# CH634W6G.net
KiCad netlist of a schematic drawn in Altium Designer
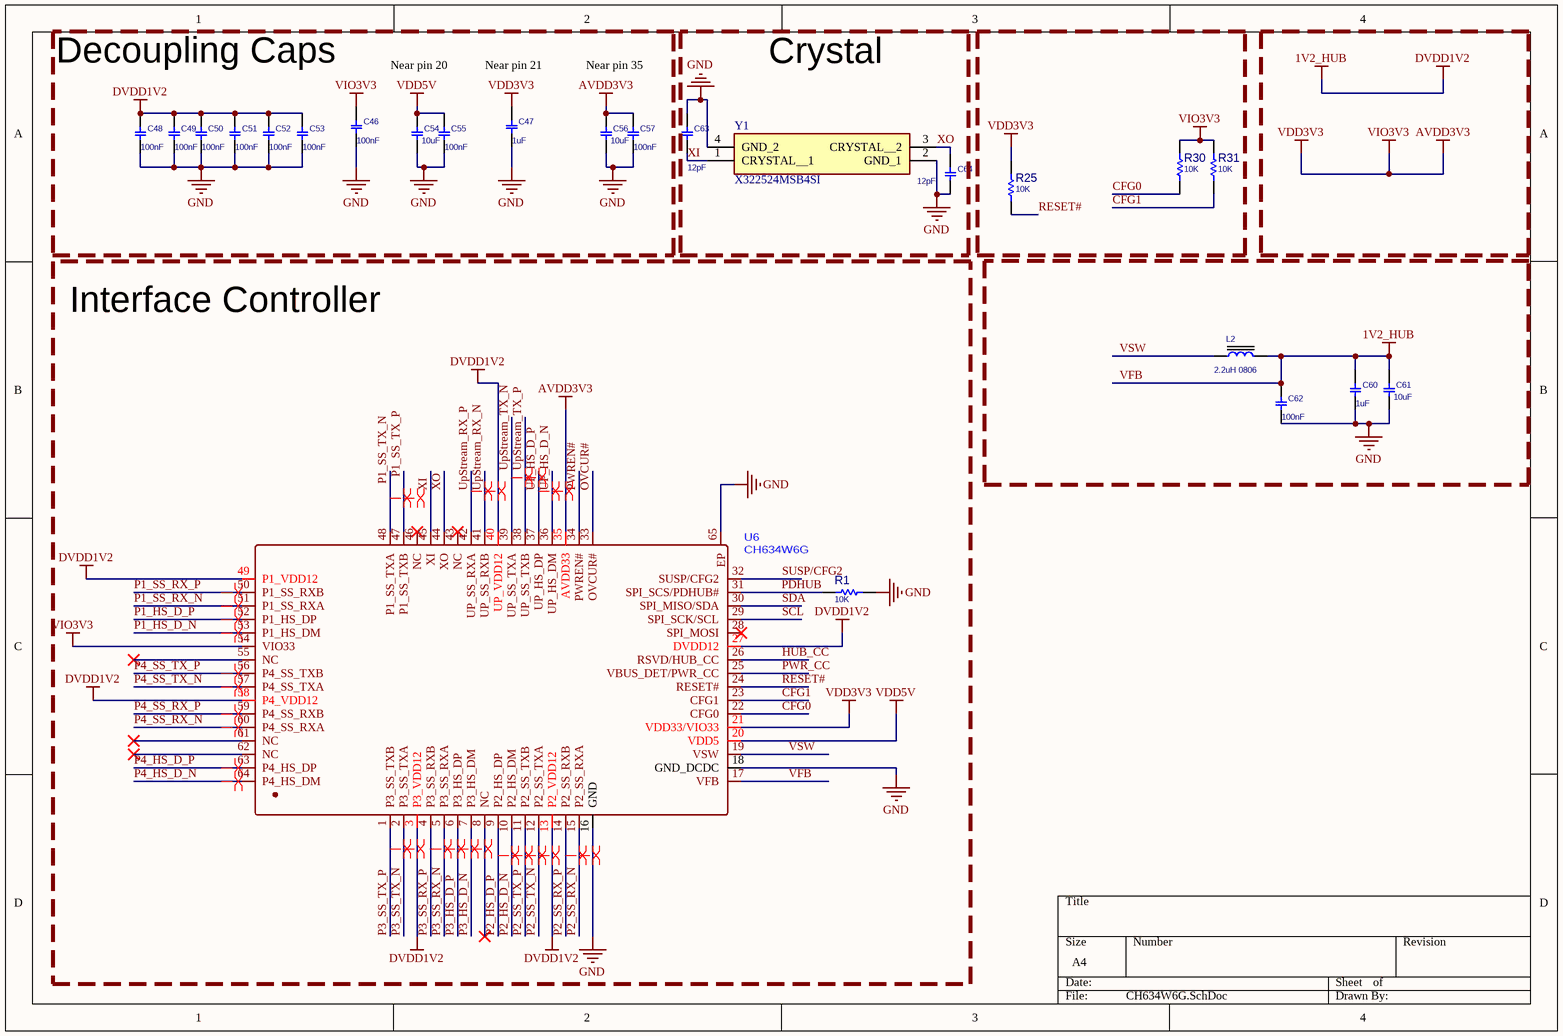
[diagram p0: CH634W6G.SchDoc]

(export (version "E")
  (design (tool "Eeschema 10.0.6"))
  (components
    (comp (ref "C46")
      (value "100nF")
      (footprint "C0402")
      (libsource (lib "passive_smd") (part "CAP_SMD_MLCC_0402"))
    )
    (comp (ref "C47")
      (value "1uF")
      (footprint "C0402")
      (libsource (lib "passive_smd") (part "CAP_SMD_MLCC_0402"))
    )
    (comp (ref "C48")
      (value "100nF")
      (footprint "C0402")
      (libsource (lib "passive_smd") (part "CAP_SMD_MLCC_0402"))
    )
    (comp (ref "C49")
      (value "100nF")
      (footprint "C0402")
      (libsource (lib "passive_smd") (part "CAP_SMD_MLCC_0402"))
    )
    (comp (ref "C50")
      (value "100nF")
      (footprint "C0402")
      (libsource (lib "passive_smd") (part "CAP_SMD_MLCC_0402"))
    )
    (comp (ref "C51")
      (value "100nF")
      (footprint "C0402")
      (libsource (lib "passive_smd") (part "CAP_SMD_MLCC_0402"))
    )
    (comp (ref "C52")
      (value "100nF")
      (footprint "C0402")
      (libsource (lib "passive_smd") (part "CAP_SMD_MLCC_0402"))
    )
    (comp (ref "C53")
      (value "100nF")
      (footprint "C0402")
      (libsource (lib "passive_smd") (part "CAP_SMD_MLCC_0402"))
    )
    (comp (ref "C54")
      (value "10uF")
      (footprint "C0603")
      (libsource (lib "passive_smd") (part "CAP_SMD_MLCC_0603"))
    )
    (comp (ref "C55")
      (value "100nF")
      (footprint "C0402")
      (libsource (lib "passive_smd") (part "CAP_SMD_MLCC_0402"))
    )
    (comp (ref "C56")
      (value "10uF")
      (footprint "C0603")
      (libsource (lib "passive_smd") (part "CAP_SMD_MLCC_0603"))
    )
    (comp (ref "C57")
      (value "100nF")
      (footprint "C0402")
      (libsource (lib "passive_smd") (part "CAP_SMD_MLCC_0402"))
    )
    (comp (ref "C60")
      (value "1uF")
      (footprint "C0402")
      (libsource (lib "passive_smd") (part "CAP_SMD_MLCC_0402"))
    )
    (comp (ref "C61")
      (value "10uF")
      (footprint "C0603")
      (libsource (lib "passive_smd") (part "CAP_SMD_MLCC_0603"))
    )
    (comp (ref "C62")
      (value "100nF")
      (footprint "C0402")
      (libsource (lib "passive_smd") (part "CAP_SMD_MLCC_0402"))
    )
    (comp (ref "C63")
      (value "12pF")
      (footprint "C0402")
      (libsource (lib "passive_smd") (part "CAP_SMD_MLCC_0402"))
    )
    (comp (ref "C64")
      (value "12pF")
      (footprint "C0402")
      (libsource (lib "passive_smd") (part "CAP_SMD_MLCC_0402"))
    )
    (comp (ref "L2")
      (value "2.2uH 0806")
      (footprint "L0806")
      (description "SLW201610S2R2MST")
      (libsource (lib "inductor_power") (part "IND_SMD_1uH_2.3A_0806"))
    )
    (comp (ref "R1")
      (value "10K")
      (footprint "R0402")
      (description "RESISTOR, SMD")
      (libsource (lib "passive_smd") (part "RES_SMD_0402"))
    )
    (comp (ref "R25")
      (value "10K")
      (footprint "R0402")
      (description "RESISTOR, SMD")
      (libsource (lib "passive_smd") (part "RES_SMD_0402"))
    )
    (comp (ref "R30")
      (value "10K")
      (footprint "R0402")
      (description "RESISTOR, SMD")
      (libsource (lib "passive_smd") (part "RES_SMD_0402"))
    )
    (comp (ref "R31")
      (value "10K")
      (footprint "R0402")
      (description "RESISTOR, SMD")
      (libsource (lib "passive_smd") (part "RES_SMD_0402"))
    )
    (comp (ref "U6") (value "CH634W6G") (footprint "CH634w") (libsource (lib "Schlib1") (part "CH634W6G")))
    (comp (ref "Y1")
      (value "X322524MSB4SI")
      (footprint "SamacSys:X1E0000210264")
      (description "Crystal or Oscillator")
      (libsource (lib "*") (part "X1E0000210264"))
    )
  )
  (nets
    (net (code "1") (name "/CFG0") (class "Default")
      (node (ref "R30") (pin "2") (pinfunction "2_2") (pintype "passive"))
      (node (ref "U6") (pin "22") (pinfunction "CFG0_22") (pintype "passive"))
    )
    (net (code "2") (name "/CFG1") (class "Default")
      (node (ref "R31") (pin "2") (pinfunction "2_2") (pintype "passive"))
      (node (ref "U6") (pin "23") (pinfunction "CFG1_23") (pintype "passive"))
    )
    (net (code "3") (name "/HUB_CC") (class "Default")
      (node (ref "U6") (pin "26") (pinfunction "RSVD/HUB_CC_26") (pintype "passive"))
    )
    (net (code "4") (name "/OVCUR#") (class "Default")
      (node (ref "U6") (pin "33") (pinfunction "OVCUR#_33") (pintype "passive"))
    )
    (net (code "5") (name "/P1_HS_D_N") (class "Default")
      (node (ref "U6") (pin "53") (pinfunction "P1_HS_DM_53") (pintype "passive"))
    )
    (net (code "6") (name "/P1_HS_D_P") (class "Default")
      (node (ref "U6") (pin "52") (pinfunction "P1_HS_DP_52") (pintype "passive"))
    )
    (net (code "7") (name "/P1_SS_RX_N") (class "Default")
      (node (ref "U6") (pin "51") (pinfunction "P1_SS_RXA_51") (pintype "passive"))
    )
    (net (code "8") (name "/P1_SS_RX_P") (class "Default")
      (node (ref "U6") (pin "50") (pinfunction "P1_SS_RXB_50") (pintype "passive"))
    )
    (net (code "9") (name "/P1_SS_TX_N") (class "Default")
      (node (ref "U6") (pin "48") (pinfunction "P1_SS_TXA_48") (pintype "passive"))
    )
    (net (code "10") (name "/P1_SS_TX_P") (class "Default")
      (node (ref "U6") (pin "47") (pinfunction "P1_SS_TXB_47") (pintype "passive"))
    )
    (net (code "11") (name "/P2_HS_D_N") (class "Default")
      (node (ref "U6") (pin "10") (pinfunction "P2_HS_DM_10") (pintype "passive"))
    )
    (net (code "12") (name "/P2_HS_D_P") (class "Default")
      (node (ref "U6") (pin "9") (pinfunction "P2_HS_DP_9") (pintype "passive"))
    )
    (net (code "13") (name "/P2_SS_RX_N") (class "Default")
      (node (ref "U6") (pin "15") (pinfunction "P2_SS_RXA_15") (pintype "passive"))
    )
    (net (code "14") (name "/P2_SS_RX_P") (class "Default")
      (node (ref "U6") (pin "14") (pinfunction "P2_SS_RXB_14") (pintype "passive"))
    )
    (net (code "15") (name "/P2_SS_TX_N") (class "Default")
      (node (ref "U6") (pin "12") (pinfunction "P2_SS_TXA_12") (pintype "passive"))
    )
    (net (code "16") (name "/P2_SS_TX_P") (class "Default")
      (node (ref "U6") (pin "11") (pinfunction "P2_SS_TXB_11") (pintype "passive"))
    )
    (net (code "17") (name "/P3_HS_D_N") (class "Default")
      (node (ref "U6") (pin "7") (pinfunction "P3_HS_DM_7") (pintype "passive"))
    )
    (net (code "18") (name "/P3_HS_D_P") (class "Default")
      (node (ref "U6") (pin "6") (pinfunction "P3_HS_DP_6") (pintype "passive"))
    )
    (net (code "19") (name "/P3_SS_RX_N") (class "Default")
      (node (ref "U6") (pin "5") (pinfunction "P3_SS_RXA_5") (pintype "passive"))
    )
    (net (code "20") (name "/P3_SS_RX_P") (class "Default")
      (node (ref "U6") (pin "4") (pinfunction "P3_SS_RXB_4") (pintype "passive"))
    )
    (net (code "21") (name "/P3_SS_TX_N") (class "Default")
      (node (ref "U6") (pin "2") (pinfunction "P3_SS_TXA_2") (pintype "passive"))
    )
    (net (code "22") (name "/P3_SS_TX_P") (class "Default")
      (node (ref "U6") (pin "1") (pinfunction "P3_SS_TXB_1") (pintype "passive"))
    )
    (net (code "23") (name "/P4_HS_D_N") (class "Default")
      (node (ref "U6") (pin "64") (pinfunction "P4_HS_DM_64") (pintype "passive"))
    )
    (net (code "24") (name "/P4_HS_D_P") (class "Default")
      (node (ref "U6") (pin "63") (pinfunction "P4_HS_DP_63") (pintype "passive"))
    )
    (net (code "25") (name "/P4_SS_RX_N") (class "Default")
      (node (ref "U6") (pin "60") (pinfunction "P4_SS_RXA_60") (pintype "passive"))
    )
    (net (code "26") (name "/P4_SS_RX_P") (class "Default")
      (node (ref "U6") (pin "59") (pinfunction "P4_SS_RXB_59") (pintype "passive"))
    )
    (net (code "27") (name "/P4_SS_TX_N") (class "Default")
      (node (ref "U6") (pin "57") (pinfunction "P4_SS_TXA_57") (pintype "passive"))
    )
    (net (code "28") (name "/P4_SS_TX_P") (class "Default")
      (node (ref "U6") (pin "56") (pinfunction "P4_SS_TXB_56") (pintype "passive"))
    )
    (net (code "29") (name "/PDHUB") (class "Default")
      (node (ref "R1") (pin "1") (pinfunction "1_1") (pintype "passive"))
      (node (ref "U6") (pin "31") (pinfunction "SPI_SCS/PDHUB#_31") (pintype "passive"))
    )
    (net (code "30") (name "/PWREN#") (class "Default")
      (node (ref "U6") (pin "34") (pinfunction "PWREN#_34") (pintype "passive"))
    )
    (net (code "31") (name "/PWR_CC") (class "Default")
      (node (ref "U6") (pin "25") (pinfunction "VBUS_DET/PWR_CC_25") (pintype "passive"))
    )
    (net (code "32") (name "/RESET#") (class "Default")
      (node (ref "R25") (pin "2") (pinfunction "2_2") (pintype "passive"))
      (node (ref "U6") (pin "24") (pinfunction "RESET#_24") (pintype "passive"))
    )
    (net (code "33") (name "/SCL") (class "Default")
      (node (ref "U6") (pin "29") (pinfunction "SPI_SCK/SCL_29") (pintype "passive"))
    )
    (net (code "34") (name "/SDA") (class "Default")
      (node (ref "U6") (pin "30") (pinfunction "SPI_MISO/SDA_30") (pintype "passive"))
    )
    (net (code "35") (name "/SUSP{slash}CFG2") (class "Default")
      (node (ref "U6") (pin "32") (pinfunction "SUSP/CFG2_32") (pintype "passive"))
    )
    (net (code "36") (name "/UP_HS_D_N") (class "Default")
      (node (ref "U6") (pin "36") (pinfunction "UP_HS_DM_36") (pintype "passive"))
    )
    (net (code "37") (name "/UP_HS_D_P") (class "Default")
      (node (ref "U6") (pin "37") (pinfunction "UP_HS_DP_37") (pintype "passive"))
    )
    (net (code "38") (name "/UpStream_RX_N") (class "Default")
      (node (ref "U6") (pin "41") (pinfunction "UP_SS_RXB_41") (pintype "passive"))
    )
    (net (code "39") (name "/UpStream_RX_P") (class "Default")
      (node (ref "U6") (pin "42") (pinfunction "UP_SS_RXA_42") (pintype "passive"))
    )
    (net (code "40") (name "/UpStream_TX_N") (class "Default")
      (node (ref "U6") (pin "39") (pinfunction "UP_SS_TXA_39") (pintype "passive"))
    )
    (net (code "41") (name "/UpStream_TX_P") (class "Default")
      (node (ref "U6") (pin "38") (pinfunction "UP_SS_TXB_38") (pintype "passive"))
    )
    (net (code "42") (name "/VSW") (class "Default")
      (node (ref "L2") (pin "1") (pinfunction "1_1") (pintype "passive"))
      (node (ref "U6") (pin "19") (pinfunction "VSW_19") (pintype "passive"))
    )
    (net (code "43") (name "/XI") (class "Default")
      (node (ref "C63") (pin "1") (pinfunction "1_1") (pintype "passive"))
      (node (ref "U6") (pin "45") (pinfunction "XI_45") (pintype "passive"))
      (node (ref "Y1") (pin "1") (pinfunction "CRYSTAL__1_1") (pintype "passive"))
    )
    (net (code "44") (name "/XO") (class "Default")
      (node (ref "C64") (pin "1") (pinfunction "1_1") (pintype "passive"))
      (node (ref "U6") (pin "44") (pinfunction "XO_44") (pintype "passive"))
      (node (ref "Y1") (pin "3") (pinfunction "CRYSTAL__2_3") (pintype "passive"))
    )
    (net (code "45") (name "1V2_HUB") (class "Default")
      (node (ref "C48") (pin "2") (pinfunction "2_2") (pintype "passive"))
      (node (ref "C49") (pin "2") (pinfunction "2_2") (pintype "passive"))
      (node (ref "C50") (pin "2") (pinfunction "2_2") (pintype "passive"))
      (node (ref "C51") (pin "2") (pinfunction "2_2") (pintype "passive"))
      (node (ref "C52") (pin "2") (pinfunction "2_2") (pintype "passive"))
      (node (ref "C53") (pin "2") (pinfunction "2_2") (pintype "passive"))
      (node (ref "C60") (pin "2") (pinfunction "2_2") (pintype "passive"))
      (node (ref "C61") (pin "2") (pinfunction "2_2") (pintype "passive"))
      (node (ref "C62") (pin "2") (pinfunction "2_2") (pintype "passive"))
      (node (ref "L2") (pin "2") (pinfunction "2_2") (pintype "passive"))
      (node (ref "U6") (pin "13") (pinfunction "P2_VDD12_13") (pintype "passive"))
      (node (ref "U6") (pin "17") (pinfunction "VFB_17") (pintype "passive"))
      (node (ref "U6") (pin "27") (pinfunction "DVDD12_27") (pintype "passive"))
      (node (ref "U6") (pin "3") (pinfunction "P3_VDD12_3") (pintype "passive"))
      (node (ref "U6") (pin "40") (pinfunction "UP_VDD12_40") (pintype "passive"))
      (node (ref "U6") (pin "49") (pinfunction "P1_VDD12_49") (pintype "passive"))
      (node (ref "U6") (pin "58") (pinfunction "P4_VDD12_58") (pintype "passive"))
    )
    (net (code "46") (name "AVDD3V3") (class "Default")
      (node (ref "C46") (pin "2") (pinfunction "2_2") (pintype "passive"))
      (node (ref "C47") (pin "2") (pinfunction "2_2") (pintype "passive"))
      (node (ref "C56") (pin "2") (pinfunction "2_2") (pintype "passive"))
      (node (ref "C57") (pin "2") (pinfunction "2_2") (pintype "passive"))
      (node (ref "R25") (pin "1") (pinfunction "1_1") (pintype "passive"))
      (node (ref "R30") (pin "1") (pinfunction "1_1") (pintype "passive"))
      (node (ref "R31") (pin "1") (pinfunction "1_1") (pintype "passive"))
      (node (ref "U6") (pin "21") (pinfunction "VDD33/VIO33_21") (pintype "passive"))
      (node (ref "U6") (pin "35") (pinfunction "AVDD33_35") (pintype "passive"))
      (node (ref "U6") (pin "54") (pinfunction "VIO33_54") (pintype "passive"))
    )
    (net (code "47") (name "GND") (class "Default")
      (node (ref "C46") (pin "1") (pinfunction "1_1") (pintype "passive"))
      (node (ref "C47") (pin "1") (pinfunction "1_1") (pintype "passive"))
      (node (ref "C48") (pin "1") (pinfunction "1_1") (pintype "passive"))
      (node (ref "C49") (pin "1") (pinfunction "1_1") (pintype "passive"))
      (node (ref "C50") (pin "1") (pinfunction "1_1") (pintype "passive"))
      (node (ref "C51") (pin "1") (pinfunction "1_1") (pintype "passive"))
      (node (ref "C52") (pin "1") (pinfunction "1_1") (pintype "passive"))
      (node (ref "C53") (pin "1") (pinfunction "1_1") (pintype "passive"))
      (node (ref "C54") (pin "1") (pinfunction "1_1") (pintype "passive"))
      (node (ref "C55") (pin "1") (pinfunction "1_1") (pintype "passive"))
      (node (ref "C56") (pin "1") (pinfunction "1_1") (pintype "passive"))
      (node (ref "C57") (pin "1") (pinfunction "1_1") (pintype "passive"))
      (node (ref "C60") (pin "1") (pinfunction "1_1") (pintype "passive"))
      (node (ref "C61") (pin "1") (pinfunction "1_1") (pintype "passive"))
      (node (ref "C62") (pin "1") (pinfunction "1_1") (pintype "passive"))
      (node (ref "C63") (pin "2") (pinfunction "2_2") (pintype "passive"))
      (node (ref "C64") (pin "2") (pinfunction "2_2") (pintype "passive"))
      (node (ref "R1") (pin "2") (pinfunction "2_2") (pintype "passive"))
      (node (ref "U6") (pin "16") (pinfunction "GND_16") (pintype "passive"))
      (node (ref "U6") (pin "18") (pinfunction "GND_DCDC_18") (pintype "passive"))
      (node (ref "U6") (pin "65") (pinfunction "EP_65") (pintype "passive"))
      (node (ref "Y1") (pin "2") (pinfunction "GND_1_2") (pintype "passive"))
      (node (ref "Y1") (pin "4") (pinfunction "GND_2_4") (pintype "passive"))
    )
    (net (code "48") (name "VDD5V") (class "Default")
      (node (ref "C54") (pin "2") (pinfunction "2_2") (pintype "passive"))
      (node (ref "C55") (pin "2") (pinfunction "2_2") (pintype "passive"))
      (node (ref "U6") (pin "20") (pinfunction "VDD5_20") (pintype "passive"))
    )
    (net (code "49") (name "unconnected-(U6-NC-Pad8)") (class "Default")
      (node (ref "U6") (pin "8") (pinfunction "NC_8") (pintype "passive+no_connect"))
    )
    (net (code "50") (name "unconnected-(U6-NC-Pad43)") (class "Default")
      (node (ref "U6") (pin "43") (pinfunction "NC_43") (pintype "passive+no_connect"))
    )
    (net (code "51") (name "unconnected-(U6-NC-Pad46)") (class "Default")
      (node (ref "U6") (pin "46") (pinfunction "NC_46") (pintype "passive+no_connect"))
    )
    (net (code "52") (name "unconnected-(U6-NC-Pad55)") (class "Default")
      (node (ref "U6") (pin "55") (pinfunction "NC_55") (pintype "passive+no_connect"))
    )
    (net (code "53") (name "unconnected-(U6-NC-Pad61)") (class "Default")
      (node (ref "U6") (pin "61") (pinfunction "NC_61") (pintype "passive+no_connect"))
    )
    (net (code "54") (name "unconnected-(U6-NC-Pad62)") (class "Default")
      (node (ref "U6") (pin "62") (pinfunction "NC_62") (pintype "passive+no_connect"))
    )
    (net (code "55") (name "unconnected-(U6-SPI_MOSI-Pad28)") (class "Default")
      (node (ref "U6") (pin "28") (pinfunction "SPI_MOSI_28") (pintype "passive+no_connect"))
    )
  )
)
